# ng-beacon-proto.net
KiCad netlist of a schematic drawn in EAGLE
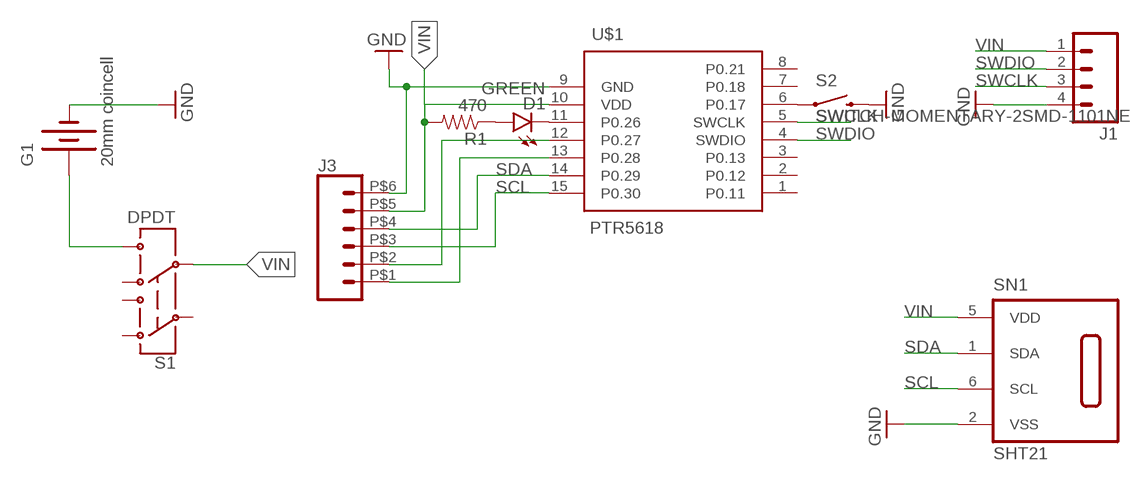
[diagram p0: schematic, sheet 1]

(export (version "E")
  (design (tool "Eeschema 10.0.6"))
  (components
    (comp (ref "D1")
      (value "GREEN")
      (footprint "eagle-import:LED-0603")
      (libsource (lib "eagle-import") (part "LED-GREEN0603"))
    )
    (comp (ref "G1")
      (value "20mm coincell")
      (footprint "eagle-import:BATTCON_20MM_4LEGS")
      (libsource (lib "eagle-import") (part "BATTERY20MM_4LEGS"))
    )
    (comp (ref "J1")
      (value "M04LOCK")
      (footprint "eagle-import:1X04_LOCK")
      (libsource (lib "eagle-import") (part "M04LOCK"))
    )
    (comp (ref "J3")
      (value "CONN_06")
      (footprint "eagle-import:PROTO4X6")
      (libsource (lib "eagle-import") (part "CONN_06"))
    )
    (comp (ref "R1")
      (value "470")
      (footprint "eagle-import:0603-RES")
      (libsource (lib "eagle-import") (part "470OHM1/10W1%(0603)"))
    )
    (comp (ref "S1")
      (value "DPDT")
      (footprint "eagle-import:AYZ0202")
      (libsource (lib "eagle-import") (part "SWITCH-DPDTAYZ0202"))
    )
    (comp (ref "S2")
      (value "SWITCH-MOMENTARY-2SMD-1101NE")
      (footprint "eagle-import:TACTILE-SWITCH-1101NE")
      (libsource (lib "eagle-import") (part "SWITCH-MOMENTARY-2SMD-1101NE"))
    )
    (comp (ref "SN1")
      (value "SHT21")
      (footprint "eagle-import:DFN6_SHT")
      (libsource (lib "eagle-import") (part "SHT21"))
    )
    (comp (ref "U$1")
      (value "PTR5618")
      (footprint "eagle-import:PTR5518")
      (libsource (lib "eagle-import") (part "PTR5618"))
    )
  )
  (nets
    (net (code "1") (name "/SCL") (class "Default")
      (node (ref "J3") (pin "P$3") (pinfunction "3_P$3") (pintype "passive"))
      (node (ref "SN1") (pin "6") (pinfunction "SCL_6") (pintype "bidirectional"))
      (node (ref "U$1") (pin "15") (pinfunction "P0.30_15") (pintype "bidirectional"))
    )
    (net (code "2") (name "/SDA") (class "Default")
      (node (ref "J3") (pin "P$4") (pinfunction "4_P$4") (pintype "passive"))
      (node (ref "SN1") (pin "1") (pinfunction "SDA_1") (pintype "bidirectional"))
      (node (ref "U$1") (pin "14") (pinfunction "P0.29_14") (pintype "bidirectional"))
    )
    (net (code "3") (name "/SWCLK") (class "Default")
      (node (ref "J1") (pin "3") (pinfunction "3_3") (pintype "passive"))
      (node (ref "U$1") (pin "5") (pinfunction "SWCLK_5") (pintype "bidirectional"))
    )
    (net (code "4") (name "/SWDIO") (class "Default")
      (node (ref "J1") (pin "2") (pinfunction "2_2") (pintype "passive"))
      (node (ref "U$1") (pin "4") (pinfunction "SWDIO_4") (pintype "bidirectional"))
    )
    (net (code "5") (name "GND") (class "Default")
      (node (ref "G1") (pin "NEGATIVE") (pinfunction "-_NEGATIVE") (pintype "power_in"))
      (node (ref "J1") (pin "4") (pinfunction "4_4") (pintype "passive"))
      (node (ref "J3") (pin "P$6") (pinfunction "6_P$6") (pintype "passive"))
      (node (ref "S2") (pin "2") (pinfunction "2_2") (pintype "passive"))
      (node (ref "SN1") (pin "2") (pinfunction "VSS_2") (pintype "power_in"))
      (node (ref "U$1") (pin "9") (pinfunction "GND_9") (pintype "power_in"))
    )
    (net (code "6") (name "Net-(D1-PadA)") (class "Default")
      (node (ref "D1") (pin "A") (pinfunction "A_A") (pintype "passive"))
      (node (ref "R1") (pin "1") (pinfunction "1_1") (pintype "passive"))
    )
    (net (code "7") (name "Net-(G1-+-PadPOSITIVE@1)") (class "Default")
      (node (ref "G1") (pin "POSITIVE@1") (pinfunction "+_POSITIVE@1") (pintype "power_in"))
      (node (ref "G1") (pin "POSITIVE@2") (pinfunction "+_POSITIVE@2") (pintype "power_in"))
      (node (ref "G1") (pin "POSITIVE@3") (pinfunction "+_POSITIVE@3") (pintype "power_in"))
      (node (ref "G1") (pin "POSITIVE@4") (pinfunction "+_POSITIVE@4") (pintype "power_in"))
      (node (ref "S1") (pin "6") (pinfunction "6_6") (pintype "bidirectional"))
    )
    (net (code "8") (name "Net-(J3-1)") (class "Default")
      (node (ref "J3") (pin "P$1") (pinfunction "1_P$1") (pintype "passive"))
      (node (ref "U$1") (pin "13") (pinfunction "P0.28_13") (pintype "bidirectional"))
    )
    (net (code "9") (name "Net-(J3-2)") (class "Default")
      (node (ref "J3") (pin "P$2") (pinfunction "2_P$2") (pintype "passive"))
      (node (ref "U$1") (pin "12") (pinfunction "P0.27_12") (pintype "bidirectional"))
    )
    (net (code "10") (name "Net-(U$1-P0.17)") (class "Default")
      (node (ref "S2") (pin "1") (pinfunction "1_1") (pintype "passive"))
      (node (ref "U$1") (pin "6") (pinfunction "P0.17_6") (pintype "bidirectional"))
    )
    (net (code "11") (name "Net-(U$1-P0.26)") (class "Default")
      (node (ref "D1") (pin "C") (pinfunction "C_C") (pintype "passive"))
      (node (ref "U$1") (pin "11") (pinfunction "P0.26_11") (pintype "bidirectional"))
    )
    (net (code "12") (name "VIN") (class "Default")
      (node (ref "J1") (pin "1") (pinfunction "1_1") (pintype "passive"))
      (node (ref "J3") (pin "P$5") (pinfunction "5_P$5") (pintype "passive"))
      (node (ref "R1") (pin "2") (pinfunction "2_2") (pintype "passive"))
      (node (ref "S1") (pin "5") (pinfunction "5_5") (pintype "bidirectional"))
      (node (ref "SN1") (pin "5") (pinfunction "VDD_5") (pintype "power_in"))
      (node (ref "U$1") (pin "10") (pinfunction "VDD_10") (pintype "power_in"))
    )
    (net (code "13") (name "unconnected-(S1-Pad1)") (class "Default")
      (node (ref "S1") (pin "1") (pinfunction "1_1") (pintype "bidirectional"))
    )
    (net (code "14") (name "unconnected-(S1-Pad2)") (class "Default")
      (node (ref "S1") (pin "2") (pinfunction "2_2") (pintype "bidirectional"))
    )
    (net (code "15") (name "unconnected-(S1-Pad3)") (class "Default")
      (node (ref "S1") (pin "3") (pinfunction "3_3") (pintype "bidirectional"))
    )
    (net (code "16") (name "unconnected-(S1-Pad4)") (class "Default")
      (node (ref "S1") (pin "4") (pinfunction "4_4") (pintype "bidirectional"))
    )
    (net (code "17") (name "unconnected-(U$1-P0.11-Pad1)") (class "Default")
      (node (ref "U$1") (pin "1") (pinfunction "P0.11_1") (pintype "bidirectional"))
    )
    (net (code "18") (name "unconnected-(U$1-P0.12-Pad2)") (class "Default")
      (node (ref "U$1") (pin "2") (pinfunction "P0.12_2") (pintype "bidirectional"))
    )
    (net (code "19") (name "unconnected-(U$1-P0.13-Pad3)") (class "Default")
      (node (ref "U$1") (pin "3") (pinfunction "P0.13_3") (pintype "bidirectional"))
    )
    (net (code "20") (name "unconnected-(U$1-P0.18-Pad7)") (class "Default")
      (node (ref "U$1") (pin "7") (pinfunction "P0.18_7") (pintype "bidirectional"))
    )
    (net (code "21") (name "unconnected-(U$1-P0.21-Pad8)") (class "Default")
      (node (ref "U$1") (pin "8") (pinfunction "P0.21_8") (pintype "bidirectional"))
    )
  )
)
